# SPK_N.net
KiCad netlist of a schematic drawn in Altium Designer
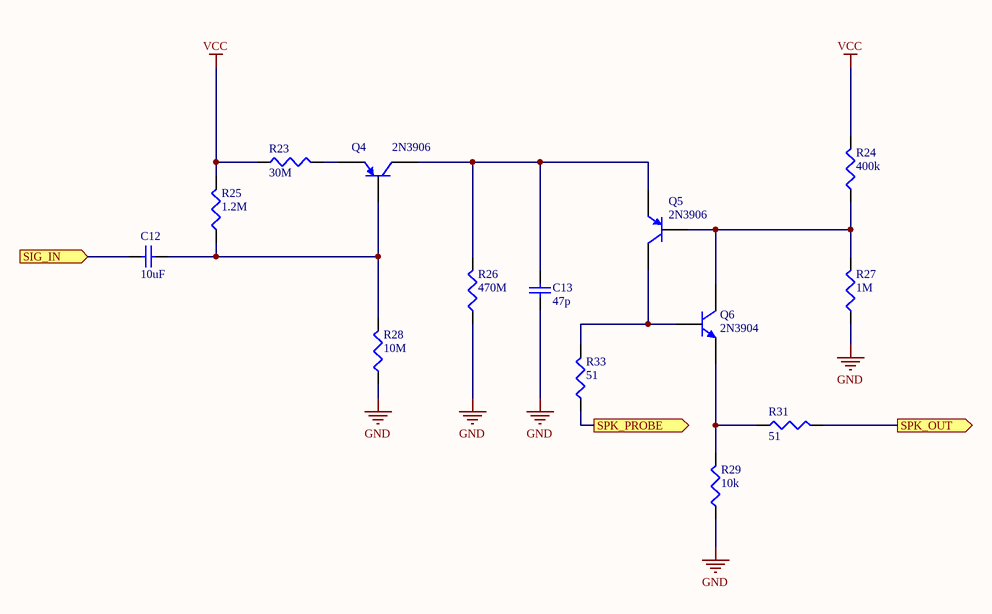
[diagram p0: SPK_N.SchDoc]

(export (version "E")
  (design (tool "Eeschema 10.0.6"))
  (components
    (comp (ref "C12")
      (value "10uF")
      (footprint "SMD-0603")
      (description "Ceramic Capacitor 0603")
      (libsource (lib "LCR") (part "CAP0603"))
    )
    (comp (ref "C13")
      (value "47p")
      (footprint "SMD-0603")
      (description "Ceramic Capacitor 0603")
      (libsource (lib "LCR") (part "CAP0603"))
    )
    (comp (ref "Q4")
      (value "2N3906")
      (footprint "TO-92A")
      (description "PNP General Purpose Amplifier")
      (fields (field (name "PUBLISHER") "Altium Limited"))
      (libsource (lib "Miscellaneous Devices") (part "2N3906"))
    )
    (comp (ref "Q5")
      (value "2N3906")
      (footprint "TO-92A")
      (description "PNP General Purpose Amplifier")
      (fields (field (name "PUBLISHER") "Altium Limited"))
      (libsource (lib "Miscellaneous Devices") (part "2N3906"))
    )
    (comp (ref "Q6")
      (value "2N3904")
      (footprint "TO-92A")
      (description "NPN General Purpose Amplifier")
      (fields (field (name "PUBLISHER") "Altium Limited"))
      (libsource (lib "Miscellaneous Devices") (part "2N3904"))
    )
    (comp (ref "R23")
      (value "30M")
      (footprint "SMD-0603")
      (description "Resistor-0603")
      (libsource (lib "LCR") (part "RES0603"))
    )
    (comp (ref "R24")
      (value "400k")
      (footprint "SMD-0603")
      (description "Resistor-0603")
      (libsource (lib "LCR") (part "RES0603"))
    )
    (comp (ref "R25")
      (value "1.2M")
      (footprint "SMD-0603")
      (description "Resistor-0603")
      (libsource (lib "LCR") (part "RES0603"))
    )
    (comp (ref "R26")
      (value "470M")
      (footprint "SMD-0603")
      (description "Resistor-0603")
      (libsource (lib "LCR") (part "RES0603"))
    )
    (comp (ref "R27")
      (value "1M")
      (footprint "SMD-0603")
      (description "Resistor-0603")
      (libsource (lib "LCR") (part "RES0603"))
    )
    (comp (ref "R28")
      (value "10M")
      (footprint "SMD-0603")
      (description "Resistor-0603")
      (libsource (lib "LCR") (part "RES0603"))
    )
    (comp (ref "R29")
      (value "10k")
      (footprint "SMD-0603")
      (description "Resistor-0603")
      (libsource (lib "LCR") (part "RES0603"))
    )
    (comp (ref "R31")
      (value "51")
      (footprint "SMD-0603")
      (description "Resistor-0603")
      (libsource (lib "LCR") (part "RES0603"))
    )
    (comp (ref "R33")
      (value "51")
      (footprint "SMD-0603")
      (description "Resistor-0603")
      (libsource (lib "LCR") (part "RES0603"))
    )
  )
  (nets
    (net (code "1") (name "/SIG_IN") (class "Default")
      (node (ref "C12") (pin "1") (pinfunction "1_1") (pintype "passive"))
    )
    (net (code "2") (name "/SPK_OUT") (class "Default")
      (node (ref "R31") (pin "2") (pinfunction "2_2") (pintype "passive"))
    )
    (net (code "3") (name "/SPK_PROBE") (class "Default")
      (node (ref "R33") (pin "1") (pinfunction "1_1") (pintype "passive"))
    )
    (net (code "4") (name "GND") (class "Default")
      (node (ref "C13") (pin "1") (pinfunction "1_1") (pintype "passive"))
      (node (ref "R26") (pin "1") (pinfunction "1_1") (pintype "passive"))
      (node (ref "R27") (pin "1") (pinfunction "1_1") (pintype "passive"))
      (node (ref "R28") (pin "1") (pinfunction "1_1") (pintype "passive"))
      (node (ref "R29") (pin "1") (pinfunction "1_1") (pintype "passive"))
    )
    (net (code "5") (name "Net-(Q4-B)") (class "Default")
      (node (ref "C12") (pin "2") (pinfunction "2_2") (pintype "passive"))
      (node (ref "Q4") (pin "2") (pinfunction "B_2") (pintype "passive"))
      (node (ref "R25") (pin "1") (pinfunction "1_1") (pintype "passive"))
      (node (ref "R28") (pin "2") (pinfunction "2_2") (pintype "passive"))
    )
    (net (code "6") (name "Net-(Q4-C)") (class "Default")
      (node (ref "C13") (pin "2") (pinfunction "2_2") (pintype "passive"))
      (node (ref "Q4") (pin "3") (pinfunction "C_3") (pintype "passive"))
      (node (ref "Q5") (pin "1") (pinfunction "E_1") (pintype "passive"))
      (node (ref "R26") (pin "2") (pinfunction "2_2") (pintype "passive"))
    )
    (net (code "7") (name "Net-(Q4-E)") (class "Default")
      (node (ref "Q4") (pin "1") (pinfunction "E_1") (pintype "passive"))
      (node (ref "R23") (pin "2") (pinfunction "2_2") (pintype "passive"))
    )
    (net (code "8") (name "Net-(Q5-B)") (class "Default")
      (node (ref "Q5") (pin "2") (pinfunction "B_2") (pintype "passive"))
      (node (ref "Q6") (pin "3") (pinfunction "C_3") (pintype "passive"))
      (node (ref "R24") (pin "1") (pinfunction "1_1") (pintype "passive"))
      (node (ref "R27") (pin "2") (pinfunction "2_2") (pintype "passive"))
    )
    (net (code "9") (name "Net-(Q5-C)") (class "Default")
      (node (ref "Q5") (pin "3") (pinfunction "C_3") (pintype "passive"))
      (node (ref "Q6") (pin "2") (pinfunction "B_2") (pintype "passive"))
      (node (ref "R33") (pin "2") (pinfunction "2_2") (pintype "passive"))
    )
    (net (code "10") (name "Net-(Q6-E)") (class "Default")
      (node (ref "Q6") (pin "1") (pinfunction "E_1") (pintype "passive"))
      (node (ref "R29") (pin "2") (pinfunction "2_2") (pintype "passive"))
      (node (ref "R31") (pin "1") (pinfunction "1_1") (pintype "passive"))
    )
    (net (code "11") (name "VCC") (class "Default")
      (node (ref "R23") (pin "1") (pinfunction "1_1") (pintype "passive"))
      (node (ref "R24") (pin "2") (pinfunction "2_2") (pintype "passive"))
      (node (ref "R25") (pin "2") (pinfunction "2_2") (pintype "passive"))
    )
  )
)
